# termoresistenza_v1_rev0.net
KiCad netlist of a schematic drawn in EAGLE
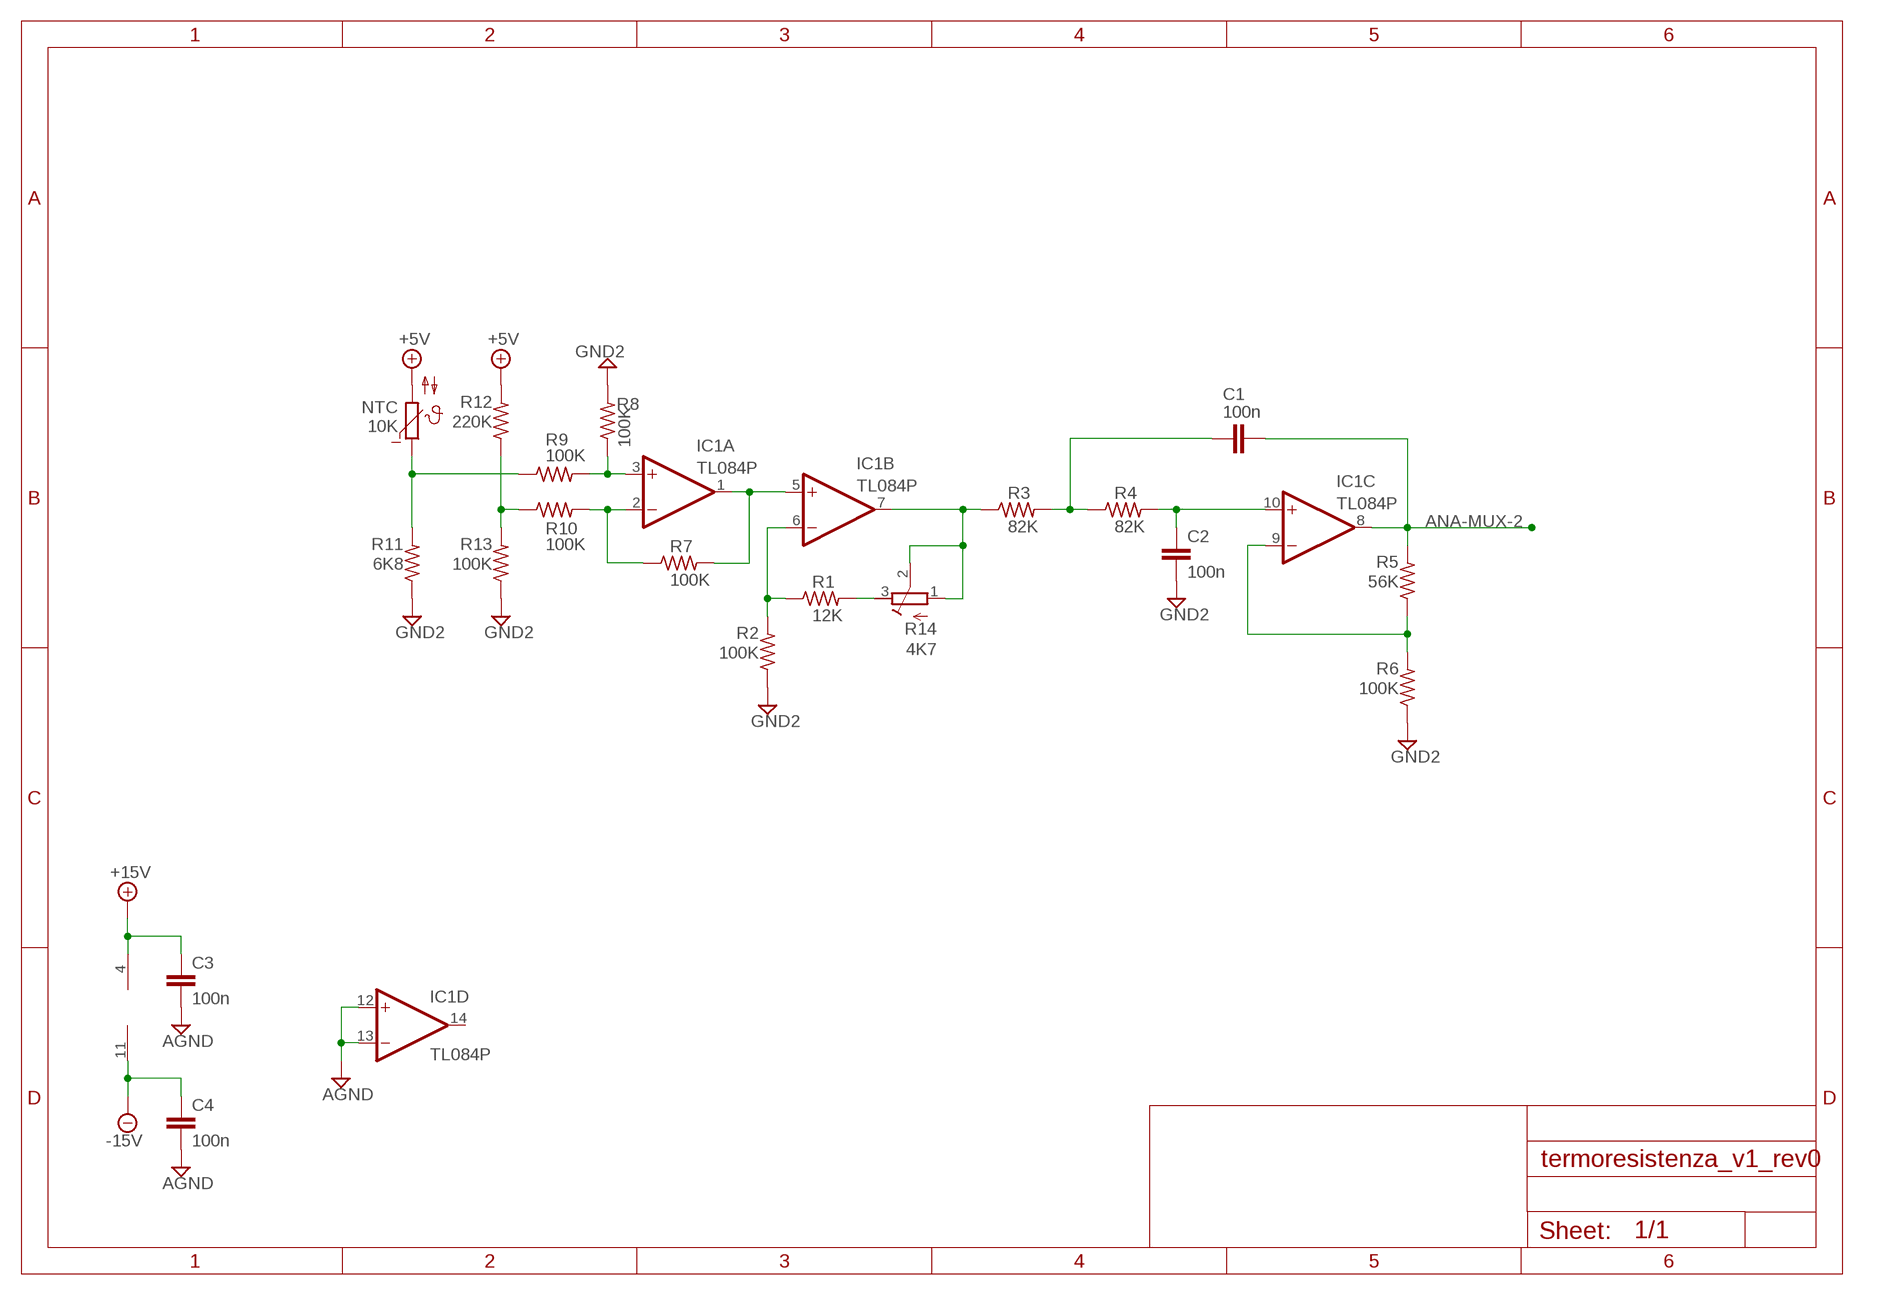
[diagram p0: schematic, sheet 1]

(export (version "E")
  (design (tool "Eeschema 10.0.6"))
  (components
    (comp (ref "C1")
      (value "100n")
      (footprint "eagle-import:C025-025X050")
      (libsource (lib "eagle-import") (part "C-EU025-025X050"))
    )
    (comp (ref "C2")
      (value "100n")
      (footprint "eagle-import:C025-025X050")
      (libsource (lib "eagle-import") (part "C-EU025-025X050"))
    )
    (comp (ref "C3")
      (value "100n")
      (footprint "eagle-import:C025-025X050")
      (libsource (lib "eagle-import") (part "C-EU025-025X050"))
    )
    (comp (ref "C4")
      (value "100n")
      (footprint "eagle-import:C025-025X050")
      (libsource (lib "eagle-import") (part "C-EU025-025X050"))
    )
    (comp (ref "IC1")
      (value "TL084P")
      (footprint "eagle-import:DIL14")
      (libsource (lib "eagle-import") (part "TL084P"))
    )
    (comp (ref "NTC")
      (value "10K")
      (footprint "eagle-import:P640")
      (libsource (lib "eagle-import") (part "NTC640"))
    )
    (comp (ref "R1")
      (value "12K")
      (footprint "eagle-import:0204_7")
      (libsource (lib "eagle-import") (part "R-US_0204/7"))
    )
    (comp (ref "R2")
      (value "100K")
      (footprint "eagle-import:0204_7")
      (libsource (lib "eagle-import") (part "R-US_0204/7"))
    )
    (comp (ref "R3")
      (value "82K")
      (footprint "eagle-import:0204_7")
      (libsource (lib "eagle-import") (part "R-US_0204/7"))
    )
    (comp (ref "R4")
      (value "82K")
      (footprint "eagle-import:0204_7")
      (libsource (lib "eagle-import") (part "R-US_0204/7"))
    )
    (comp (ref "R5")
      (value "56K")
      (footprint "eagle-import:0204_7")
      (libsource (lib "eagle-import") (part "R-US_0204/7"))
    )
    (comp (ref "R6")
      (value "100K")
      (footprint "eagle-import:0204_7")
      (libsource (lib "eagle-import") (part "R-US_0204/7"))
    )
    (comp (ref "R7")
      (value "100K")
      (footprint "eagle-import:0204_7")
      (libsource (lib "eagle-import") (part "R-US_0204/7"))
    )
    (comp (ref "R8")
      (value "100K")
      (footprint "eagle-import:0204_7")
      (libsource (lib "eagle-import") (part "R-US_0204/7"))
    )
    (comp (ref "R9")
      (value "100K")
      (footprint "eagle-import:0204_7")
      (libsource (lib "eagle-import") (part "R-US_0204/7"))
    )
    (comp (ref "R10")
      (value "100K")
      (footprint "eagle-import:0204_7")
      (libsource (lib "eagle-import") (part "R-US_0204/7"))
    )
    (comp (ref "R11")
      (value "6K8")
      (footprint "eagle-import:0204_7")
      (libsource (lib "eagle-import") (part "R-US_0204/7"))
    )
    (comp (ref "R12")
      (value "220K")
      (footprint "eagle-import:0204_7")
      (libsource (lib "eagle-import") (part "R-US_0204/7"))
    )
    (comp (ref "R13")
      (value "100K")
      (footprint "eagle-import:0204_7")
      (libsource (lib "eagle-import") (part "R-US_0204/7"))
    )
    (comp (ref "R14")
      (value "4K7")
      (footprint "eagle-import:RTRIM64W")
      (libsource (lib "eagle-import") (part "R-TRIMM64W"))
    )
  )
  (nets
    (net (code "1") (name "+5V") (class "Default")
      (node (ref "NTC") (pin "2") (pinfunction "2_2") (pintype "passive"))
      (node (ref "R12") (pin "2") (pinfunction "2_2") (pintype "passive"))
    )
    (net (code "2") (name "+15V") (class "Default")
      (node (ref "C3") (pin "1") (pinfunction "1_1") (pintype "passive"))
      (node (ref "IC1") (pin "4") (pinfunction "V+_4") (pintype "power_in"))
    )
    (net (code "3") (name "-15V") (class "Default")
      (node (ref "C4") (pin "1") (pinfunction "1_1") (pintype "passive"))
      (node (ref "IC1") (pin "11") (pinfunction "V-_11") (pintype "power_in"))
    )
    (net (code "4") (name "/ANA-MUX-2") (class "Default")
      (node (ref "C1") (pin "2") (pinfunction "2_2") (pintype "passive"))
      (node (ref "IC1") (pin "8") (pinfunction "OUT_8") (pintype "output"))
      (node (ref "R5") (pin "2") (pinfunction "2_2") (pintype "passive"))
    )
    (net (code "5") (name "AGND") (class "Default")
      (node (ref "C3") (pin "2") (pinfunction "2_2") (pintype "passive"))
      (node (ref "C4") (pin "2") (pinfunction "2_2") (pintype "passive"))
      (node (ref "IC1") (pin "12") (pinfunction "+IN_12") (pintype "input"))
      (node (ref "IC1") (pin "13") (pinfunction "-IN_13") (pintype "input"))
    )
    (net (code "6") (name "GND2") (class "Default")
      (node (ref "C2") (pin "2") (pinfunction "2_2") (pintype "passive"))
      (node (ref "R11") (pin "1") (pinfunction "1_1") (pintype "passive"))
      (node (ref "R13") (pin "1") (pinfunction "1_1") (pintype "passive"))
      (node (ref "R2") (pin "1") (pinfunction "1_1") (pintype "passive"))
      (node (ref "R6") (pin "1") (pinfunction "1_1") (pintype "passive"))
      (node (ref "R8") (pin "2") (pinfunction "2_2") (pintype "passive"))
    )
    (net (code "7") (name "Net-(C1-Pad1)") (class "Default")
      (node (ref "C1") (pin "1") (pinfunction "1_1") (pintype "passive"))
      (node (ref "R3") (pin "2") (pinfunction "2_2") (pintype "passive"))
      (node (ref "R4") (pin "1") (pinfunction "1_1") (pintype "passive"))
    )
    (net (code "8") (name "Net-(IC1A-+IN)") (class "Default")
      (node (ref "IC1") (pin "3") (pinfunction "+IN_3") (pintype "input"))
      (node (ref "R8") (pin "1") (pinfunction "1_1") (pintype "passive"))
      (node (ref "R9") (pin "2") (pinfunction "2_2") (pintype "passive"))
    )
    (net (code "9") (name "Net-(IC1A--IN)") (class "Default")
      (node (ref "IC1") (pin "2") (pinfunction "-IN_2") (pintype "input"))
      (node (ref "R10") (pin "2") (pinfunction "2_2") (pintype "passive"))
      (node (ref "R7") (pin "1") (pinfunction "1_1") (pintype "passive"))
    )
    (net (code "10") (name "Net-(IC1A-OUT)") (class "Default")
      (node (ref "IC1") (pin "1") (pinfunction "OUT_1") (pintype "output"))
      (node (ref "IC1") (pin "5") (pinfunction "+IN_5") (pintype "input"))
      (node (ref "R7") (pin "2") (pinfunction "2_2") (pintype "passive"))
    )
    (net (code "11") (name "Net-(IC1B--IN)") (class "Default")
      (node (ref "IC1") (pin "6") (pinfunction "-IN_6") (pintype "input"))
      (node (ref "R1") (pin "1") (pinfunction "1_1") (pintype "passive"))
      (node (ref "R2") (pin "2") (pinfunction "2_2") (pintype "passive"))
    )
    (net (code "12") (name "Net-(IC1B-OUT)") (class "Default")
      (node (ref "IC1") (pin "7") (pinfunction "OUT_7") (pintype "output"))
      (node (ref "R14") (pin "1") (pinfunction "E_1") (pintype "passive"))
      (node (ref "R14") (pin "2") (pinfunction "S_2") (pintype "passive"))
      (node (ref "R3") (pin "1") (pinfunction "1_1") (pintype "passive"))
    )
    (net (code "13") (name "Net-(IC1C-+IN)") (class "Default")
      (node (ref "C2") (pin "1") (pinfunction "1_1") (pintype "passive"))
      (node (ref "IC1") (pin "10") (pinfunction "+IN_10") (pintype "input"))
      (node (ref "R4") (pin "2") (pinfunction "2_2") (pintype "passive"))
    )
    (net (code "14") (name "Net-(IC1C--IN)") (class "Default")
      (node (ref "IC1") (pin "9") (pinfunction "-IN_9") (pintype "input"))
      (node (ref "R5") (pin "1") (pinfunction "1_1") (pintype "passive"))
      (node (ref "R6") (pin "2") (pinfunction "2_2") (pintype "passive"))
    )
    (net (code "15") (name "Net-(NTC-Pad1)") (class "Default")
      (node (ref "NTC") (pin "1") (pinfunction "1_1") (pintype "passive"))
      (node (ref "R11") (pin "2") (pinfunction "2_2") (pintype "passive"))
      (node (ref "R9") (pin "1") (pinfunction "1_1") (pintype "passive"))
    )
    (net (code "16") (name "Net-(R10-Pad1)") (class "Default")
      (node (ref "R10") (pin "1") (pinfunction "1_1") (pintype "passive"))
      (node (ref "R12") (pin "1") (pinfunction "1_1") (pintype "passive"))
      (node (ref "R13") (pin "2") (pinfunction "2_2") (pintype "passive"))
    )
    (net (code "17") (name "Net-(R14-A)") (class "Default")
      (node (ref "R1") (pin "2") (pinfunction "2_2") (pintype "passive"))
      (node (ref "R14") (pin "3") (pinfunction "A_3") (pintype "passive"))
    )
    (net (code "18") (name "unconnected-(IC1D-OUT-Pad14)") (class "Default")
      (node (ref "IC1") (pin "14") (pinfunction "OUT_14") (pintype "output"))
    )
  )
)
